# MD015A_MCU_F5529.net
KiCad netlist of a schematic drawn in Altium Designer
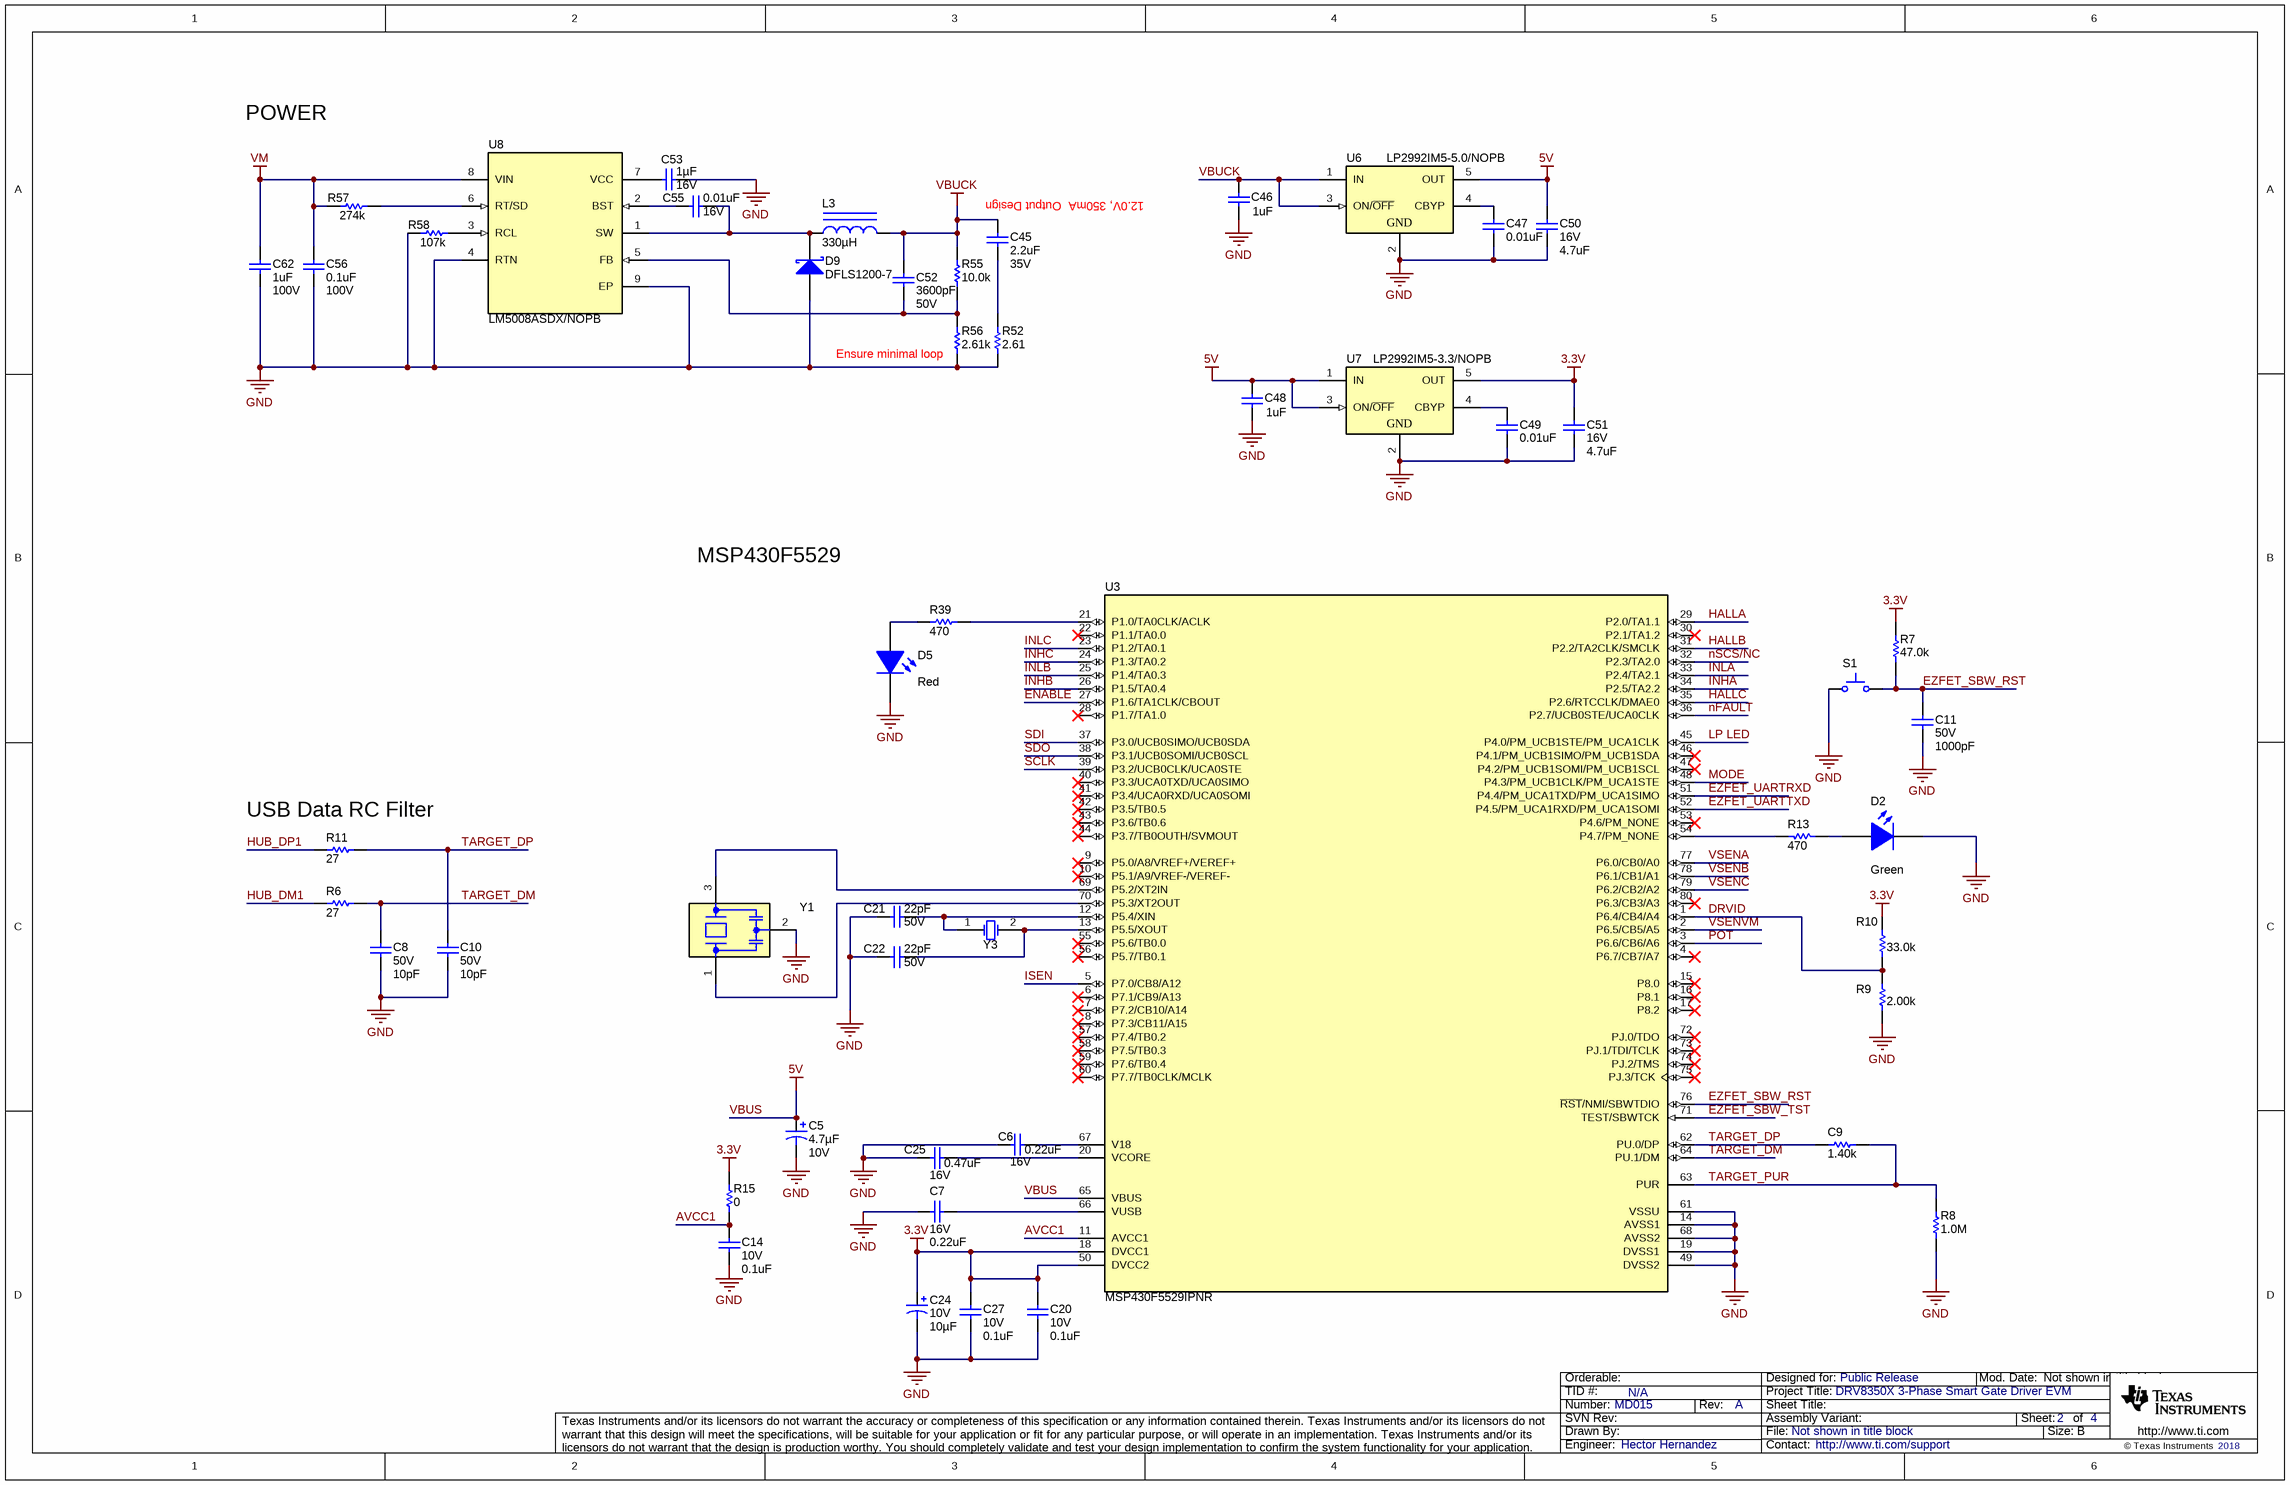
[diagram p0: MD015A_MCU_F5529.SchDoc]

(export (version "E")
  (design (tool "Eeschema 10.0.6"))
  (components
    (comp (ref "C5")
      (value "T55A475M010C0500")
      (footprint "3216-18")
      (description "CAP, Tantalum Polymer, 4.7 µF, 10 V,+/- 20%, 0.5 ohm, 3216-18 SMD")
      (fields
        (field (name "VALUEDISPLAYED") "4.7µF")
        (field (name "VDC_V") "10V")
        (field (name "MANUFACTURER") "Vishay-Sprague")
      )
      (libsource (lib "Altium Vault - TI") (part "Cap_Polarized"))
    )
    (comp (ref "C6")
      (value "C1005X5R1C224K050BB")
      (footprint "0402L")
      (description "CAP, CERM, 0.22 uF, 16 V, +/- 10%, X5R, 0402")
      (fields
        (field (name "MANUFACTURER") "TDK")
        (field (name "VDC_V") "16V")
        (field (name "VALUEDISPLAYED") "0.22uF")
        (field (name "PUBLISHER") "Texas Instruments")
      )
      (libsource (lib "Altium Vault - TI") (part "Capacitor"))
    )
    (comp (ref "C7")
      (value "C1005X5R1C224K050BB")
      (footprint "0402L")
      (description "CAP, CERM, 0.22 uF, 16 V, +/- 10%, X5R, 0402")
      (fields
        (field (name "MANUFACTURER") "TDK")
        (field (name "VDC_V") "16V")
        (field (name "VALUEDISPLAYED") "0.22uF")
        (field (name "PUBLISHER") "Texas Instruments")
      )
      (libsource (lib "Altium Vault - TI") (part "Capacitor"))
    )
    (comp (ref "C8")
      (value "500R07S100JV4T")
      (footprint "0402L")
      (description "CAP, CERM, 10 pF, 50 V, +/- 5%, C0G/NP0, 0402")
      (fields
        (field (name "MANUFACTURER") "Johanson Technology")
        (field (name "VDC_V") "50V")
        (field (name "VALUEDISPLAYED") "10pF")
        (field (name "PUBLISHER") "Texas Instruments")
      )
      (libsource (lib "Altium Vault - TI") (part "Capacitor"))
    )
    (comp (ref "C9")
      (value "ERJ-2RKF1401X")
      (footprint "0402L")
      (description "RES, 1.40 k, 1%, 0.1 W, 0402")
      (fields
        (field (name "MANUFACTURER") "Panasonic")
        (field (name "VALUEDISPLAYED") "1.40k")
        (field (name "PUBLISHER") "Texas Instruments")
      )
      (libsource (lib "Altium Vault - TI") (part "Resistor"))
    )
    (comp (ref "C10")
      (value "500R07S100JV4T")
      (footprint "0402L")
      (description "CAP, CERM, 10 pF, 50 V, +/- 5%, C0G/NP0, 0402")
      (fields
        (field (name "MANUFACTURER") "Johanson Technology")
        (field (name "VDC_V") "50V")
        (field (name "VALUEDISPLAYED") "10pF")
        (field (name "PUBLISHER") "Texas Instruments")
      )
      (libsource (lib "Altium Vault - TI") (part "Capacitor"))
    )
    (comp (ref "C11")
      (value "885012205061")
      (footprint "0402L")
      (description "CAP, CERM, 1000 pF, 50 V, +/- 10%, X7R, 0402")
      (fields
        (field (name "MANUFACTURER") "Wurth Elektronik")
        (field (name "VDC_V") "50V")
        (field (name "VALUEDISPLAYED") "1000pF")
        (field (name "PUBLISHER") "Texas Instruments")
      )
      (libsource (lib "Altium Vault - TI") (part "Capacitor"))
    )
    (comp (ref "C14")
      (value "885012105010")
      (footprint "0402L")
      (description "CAP, CERM, 0.1 uF, 10 V, +/- 20%, X5R, 0402")
      (fields
        (field (name "MANUFACTURER") "Wurth Elektronik")
        (field (name "VDC_V") "10V")
        (field (name "VALUEDISPLAYED") "0.1uF")
        (field (name "PUBLISHER") "Texas Instruments")
      )
      (libsource (lib "Altium Vault - TI") (part "Capacitor"))
    )
    (comp (ref "C20")
      (value "885012105010")
      (footprint "0402L")
      (description "CAP, CERM, 0.1 uF, 10 V, +/- 20%, X5R, 0402")
      (fields
        (field (name "MANUFACTURER") "Wurth Elektronik")
        (field (name "VDC_V") "10V")
        (field (name "VALUEDISPLAYED") "0.1uF")
        (field (name "PUBLISHER") "Texas Instruments")
      )
      (libsource (lib "Altium Vault - TI") (part "Capacitor"))
    )
    (comp (ref "C21")
      (value "C1005C0G1H220J050BA")
      (footprint "0402L")
      (description "CAP, CERM, 22 pF, 50 V, +/- 5%, C0G/NP0, 0402")
      (fields
        (field (name "MANUFACTURER") "TDK")
        (field (name "VDC_V") "50V")
        (field (name "VALUEDISPLAYED") "22pF")
        (field (name "PUBLISHER") "Texas Instruments")
      )
      (libsource (lib "Altium Vault - TI") (part "Capacitor"))
    )
    (comp (ref "C22")
      (value "C1005C0G1H220J050BA")
      (footprint "0402L")
      (description "CAP, CERM, 22 pF, 50 V, +/- 5%, C0G/NP0, 0402")
      (fields
        (field (name "MANUFACTURER") "TDK")
        (field (name "VDC_V") "50V")
        (field (name "VALUEDISPLAYED") "22pF")
        (field (name "PUBLISHER") "Texas Instruments")
      )
      (libsource (lib "Altium Vault - TI") (part "Capacitor"))
    )
    (comp (ref "C24")
      (value "T520A106M010ATE080")
      (footprint "3216-18")
      (description "CAP, Tantalum Polymer, 10 µF, 10 V,+/- 20%, 0.08 ohm, 3216-18 SMD")
      (fields
        (field (name "VDC_V") "10V")
        (field (name "MANUFACTURER") "Kemet")
        (field (name "VALUEDISPLAYED") "10µF")
      )
      (libsource (lib "Altium Vault - TI") (part "Cap_Polarized"))
    )
    (comp (ref "C25")
      (value "GCM188R71C474KA55D")
      (footprint "0603L")
      (description "CAP, CERM, 0.47 uF, 16 V, +/- 10%, X7R, AEC-Q200 Grade 1, 0603")
      (fields
        (field (name "MANUFACTURER") "MuRata")
        (field (name "VDC_V") "16V")
        (field (name "VALUEDISPLAYED") "0.47uF")
        (field (name "PUBLISHER") "Texas Instruments")
      )
      (libsource (lib "Altium Vault - TI") (part "Capacitor"))
    )
    (comp (ref "C27")
      (value "885012105010")
      (footprint "0402L")
      (description "CAP, CERM, 0.1 uF, 10 V, +/- 20%, X5R, 0402")
      (fields
        (field (name "MANUFACTURER") "Wurth Elektronik")
        (field (name "VDC_V") "10V")
        (field (name "VALUEDISPLAYED") "0.1uF")
        (field (name "PUBLISHER") "Texas Instruments")
      )
      (libsource (lib "Altium Vault - TI") (part "Capacitor"))
    )
    (comp (ref "C45")
      (value "C2012X7R1V225K085AC")
      (footprint "0805L")
      (description "CAP, CERM, 2.2 uF, 35 V, +/- 10%, X7R, 0805")
      (fields
        (field (name "MANUFACTURER") "TDK")
        (field (name "VALUEDISPLAYED") "2.2uF")
        (field (name "VDC_V") "35V")
        (field (name "PUBLISHER") "Texas Instruments")
      )
      (libsource (lib "Altium Vault - TI") (part "Capacitor"))
    )
    (comp (ref "C46")
      (value "CL21B105KBFNNNE")
      (footprint "0805L")
      (description "CAP, CERM, 1 uF, 50 V, +/- 10%, X7R, 0805")
      (fields
        (field (name "MANUFACTURER") "Samsung Electro-Mechanics")
        (field (name "VALUEDISPLAYED") "1uF")
        (field (name "PUBLISHER") "Texas Instruments")
      )
      (libsource (lib "Altium Vault - TI") (part "CMP-0007994-2"))
    )
    (comp (ref "C47")
      (value "C0603C103K4RACTU")
      (footprint "0603L")
      (description "CAP, CERM, 0.01 uF, 16 V, +/- 10%, X7R, 0603")
      (fields
        (field (name "VALUEDISPLAYED") "0.01uF")
        (field (name "MANUFACTURER") "Kemet")
        (field (name "PUBLISHER") "Texas Instruments")
      )
      (libsource (lib "Altium Vault - TI") (part "Capacitor"))
    )
    (comp (ref "C48")
      (value "CL21B105KBFNNNE")
      (footprint "0805L")
      (description "CAP, CERM, 1 uF, 50 V, +/- 10%, X7R, 0805")
      (fields
        (field (name "MANUFACTURER") "Samsung Electro-Mechanics")
        (field (name "VALUEDISPLAYED") "1uF")
        (field (name "PUBLISHER") "Texas Instruments")
      )
      (libsource (lib "Altium Vault - TI") (part "CMP-0007994-2"))
    )
    (comp (ref "C49")
      (value "C0603C103K4RACTU")
      (footprint "0603L")
      (description "CAP, CERM, 0.01 uF, 16 V, +/- 10%, X7R, 0603")
      (fields
        (field (name "VALUEDISPLAYED") "0.01uF")
        (field (name "MANUFACTURER") "Kemet")
        (field (name "PUBLISHER") "Texas Instruments")
      )
      (libsource (lib "Altium Vault - TI") (part "Capacitor"))
    )
    (comp (ref "C50")
      (value "GRM21BR71C475KA73L")
      (footprint "0805L")
      (description "CAP, CERM, 4.7 uF, 16 V, +/- 10%, X7R, 0805")
      (fields
        (field (name "MANUFACTURER") "MuRata")
        (field (name "VDC_V") "16V")
        (field (name "VALUEDISPLAYED") "4.7uF")
        (field (name "PUBLISHER") "Texas Instruments")
      )
      (libsource (lib "Altium Vault - TI") (part "Capacitor"))
    )
    (comp (ref "C51")
      (value "GRM21BR71C475KA73L")
      (footprint "0805L")
      (description "CAP, CERM, 4.7 uF, 16 V, +/- 10%, X7R, 0805")
      (fields
        (field (name "MANUFACTURER") "MuRata")
        (field (name "VDC_V") "16V")
        (field (name "VALUEDISPLAYED") "4.7uF")
        (field (name "PUBLISHER") "Texas Instruments")
      )
      (libsource (lib "Altium Vault - TI") (part "Capacitor"))
    )
    (comp (ref "C52")
      (value "GRM1885C1H362JA01D")
      (footprint "0603L")
      (description "CAP, CERM, 3600 pF, 50 V, +/- 5%, C0G/NP0, 0603")
      (fields
        (field (name "MANUFACTURER") "MuRata")
        (field (name "VALUEDISPLAYED") "3600pF")
        (field (name "VDC_V") "50V")
        (field (name "PUBLISHER") "Texas Instruments")
      )
      (libsource (lib "Altium Vault - TI") (part "Capacitor"))
    )
    (comp (ref "C53")
      (value "CL10B105KO8VPNC")
      (footprint "0603")
      (description "CAP, CERM, 1 µF, 16 V,+/- 10%, X7R, AEC-Q200 Grade 1, 0603")
      (fields
        (field (name "VDC_V") "16V")
        (field (name "MANUFACTURER") "Samsung Electro-Mechanics")
        (field (name "VALUEDISPLAYED") "1µF")
      )
      (libsource (lib "Altium Vault - TI") (part "Capacitor"))
    )
    (comp (ref "C55")
      (value "C0603C103K4RACTU")
      (footprint "0603L")
      (description "CAP, CERM, 0.01 uF, 16 V, +/- 10%, X7R, 0603")
      (fields
        (field (name "MANUFACTURER") "Kemet")
        (field (name "VALUEDISPLAYED") "0.01uF")
        (field (name "VDC_V") "16V")
        (field (name "PUBLISHER") "Texas Instruments")
      )
      (libsource (lib "Altium Vault - TI") (part "Capacitor"))
    )
    (comp (ref "C56")
      (value "C2012X7R2A104K125AA")
      (footprint "0805_HV")
      (description "CAP, CERM, 0.1 uF, 100 V, +/- 10%, X7R, 0805")
      (fields
        (field (name "MANUFACTURER") "TDK")
        (field (name "VALUEDISPLAYED") "0.1uF")
        (field (name "VDC_V") "100V")
        (field (name "PUBLISHER") "Texas Instruments")
      )
      (libsource (lib "Altium Vault - TI") (part "Capacitor"))
    )
    (comp (ref "C62")
      (value "CL31B105KCHNNNE")
      (footprint "1206_180")
      (description "CAP, CERM, 1 uF, 100 V, +/- 10%, X7R, 1206")
      (fields
        (field (name "MANUFACTURER") "Samsung")
        (field (name "VALUEDISPLAYED") "1uF")
        (field (name "VDC_V") "100V")
        (field (name "PUBLISHER") "Texas Instruments")
      )
      (libsource (lib "Altium Vault - TI") (part "Capacitor"))
    )
    (comp (ref "D2")
      (value "Green")
      (footprint "LED_LTST-C190")
      (description "LED, Green, SMD")
      (fields (field (name "MANUFACTURER") "Lite-On") (field (name "PARTNUMBER") "LTST-C190GKT"))
      (libsource (lib "Altium Vault - TI") (part "LED"))
    )
    (comp (ref "D5")
      (value "Red")
      (footprint "LED_LTST-C190_Red")
      (description "LED, Red, SMD")
      (fields (field (name "MANUFACTURER") "Lite-On") (field (name "PARTNUMBER") "LTST-C190CKT"))
      (libsource (lib "Altium Vault - TI") (part "LED"))
    )
    (comp (ref "D9")
      (value "DFLS1200-7")
      (footprint "PowerDI123")
      (description "Diode, Schottky, 200 V, 1 A, PowerDI123")
      (fields (field (name "MANUFACTURER") "Diodes Inc."))
      (libsource (lib "Altium Vault - TI") (part "DIODE_SCHOTTKY"))
    )
    (comp (ref "L3")
      (value "74404084331")
      (footprint "WE-LQS_8040")
      (description "Inductor, Shielded, 330 µH, 0.66 A, 1.1245 ohm, SMD")
      (fields (field (name "MANUFACTURER") "Wurth Elektronik") (field (name "VALUEDISPLAYED") "330µH"))
      (libsource (lib "Altium Vault - TI") (part "Inductor_Iron"))
    )
    (comp (ref "R6")
      (value "CRCW040227R0JNED")
      (footprint "0402L")
      (description "RES, 27, 5%, 0.063 W, AEC-Q200 Grade 0, 0402")
      (fields (field (name "MANUFACTURER") "Vishay-Dale") (field (name "VALUEDISPLAYED") "27"))
      (libsource (lib "Altium Vault - TI") (part "Resistor"))
    )
    (comp (ref "R7")
      (value "RC0402FR-0747KL")
      (footprint "0402L")
      (description "RES, 47.0 k, 1%, 0.0625 W, 0402")
      (fields
        (field (name "MANUFACTURER") "Yageo America")
        (field (name "VALUEDISPLAYED") "47.0k")
        (field (name "PUBLISHER") "Texas Instruments")
      )
      (libsource (lib "Altium Vault - TI") (part "Resistor"))
    )
    (comp (ref "R8")
      (value "CRCW04021M00JNED")
      (footprint "0402L")
      (description "RES, 1.0 M, 5%, 0.063 W, AEC-Q200 Grade 0, 0402")
      (fields (field (name "MANUFACTURER") "Vishay-Dale") (field (name "VALUEDISPLAYED") "1.0M"))
      (libsource (lib "Altium Vault - TI") (part "Resistor"))
    )
    (comp (ref "R9")
      (value "RC0603FR-072KL")
      (footprint "0603L")
      (description "RES, 2.00 k, 1%, 0.1 W, 0603")
      (fields (field (name "MANUFACTURER") "Yageo") (field (name "VALUEDISPLAYED") "2.00k"))
      (libsource (lib "Altium Vault - TI") (part "Resistor"))
    )
    (comp (ref "R10")
      (value "MCT06030C3302FP500")
      (footprint "0603L")
      (description "RES, 33.0 k, 1%, 0.125 W, 0603")
      (fields
        (field (name "MANUFACTURER") "Vishay/Beyschlag")
        (field (name "VALUEDISPLAYED") "33.0k")
        (field (name "PUBLISHER") "Texas Instruments")
      )
      (libsource (lib "Altium Vault - TI") (part "Resistor"))
    )
    (comp (ref "R11")
      (value "CRCW040227R0JNED")
      (footprint "0402L")
      (description "RES, 27, 5%, 0.063 W, AEC-Q200 Grade 0, 0402")
      (fields (field (name "MANUFACTURER") "Vishay-Dale") (field (name "VALUEDISPLAYED") "27"))
      (libsource (lib "Altium Vault - TI") (part "Resistor"))
    )
    (comp (ref "R13")
      (value "ERJ-2RKF4700X")
      (footprint "0402L")
      (description "RES, 470, 1%, 0.1 W, AEC-Q200 Grade 0, 0402")
      (fields
        (field (name "MANUFACTURER") "Panasonic")
        (field (name "VALUEDISPLAYED") "470")
        (field (name "PUBLISHER") "Texas Instruments")
      )
      (libsource (lib "Altium Vault - TI") (part "Resistor"))
    )
    (comp (ref "R15")
      (value "MCR01MZPJ000")
      (footprint "0402L")
      (description "RES, 0, 5%, 0.063 W, 0402")
      (fields
        (field (name "MANUFACTURER") "Rohm")
        (field (name "VALUEDISPLAYED") "0")
        (field (name "PUBLISHER") "Texas Instruments")
      )
      (libsource (lib "Altium Vault - TI") (part "Resistor"))
    )
    (comp (ref "R39")
      (value "ERJ-2RKF4700X")
      (footprint "0402L")
      (description "RES, 470, 1%, 0.1 W, AEC-Q200 Grade 0, 0402")
      (fields
        (field (name "MANUFACTURER") "Panasonic")
        (field (name "VALUEDISPLAYED") "470")
        (field (name "PUBLISHER") "Texas Instruments")
      )
      (libsource (lib "Altium Vault - TI") (part "Resistor"))
    )
    (comp (ref "R52")
      (value "CRCW06032R61FKEA")
      (footprint "0603L")
      (description "RES, 2.61, 1%, 0.1 W, AEC-Q200 Grade 0, 0603")
      (fields (field (name "MANUFACTURER") "Vishay-Dale") (field (name "VALUEDISPLAYED") "2.61"))
      (libsource (lib "Altium Vault - TI") (part "Resistor"))
    )
    (comp (ref "R55")
      (value "RG1608P-103-B-T5")
      (footprint "0603L")
      (description "RES, 10.0 k, 0.1%, 0.1 W, 0603")
      (fields
        (field (name "MANUFACTURER") "Susumu Co Ltd")
        (field (name "VALUEDISPLAYED") "10.0k")
        (field (name "PUBLISHER") "Texas Instruments")
      )
      (libsource (lib "Altium Vault - TI") (part "Resistor"))
    )
    (comp (ref "R56")
      (value "RG1608P-2611-B-T5")
      (footprint "0603L")
      (description "RES, 2.61 k, 0.1%, 0.1 W, 0603")
      (fields
        (field (name "MANUFACTURER") "Susumu Co Ltd")
        (field (name "VALUEDISPLAYED") "2.61k")
        (field (name "PUBLISHER") "Texas Instruments")
      )
      (libsource (lib "Altium Vault - TI") (part "Resistor"))
    )
    (comp (ref "R57")
      (value "RC0603FR-07274KL")
      (footprint "0603_HV")
      (description "RES, 274 k, 1%, 0.1 W, 0603")
      (fields (field (name "MANUFACTURER") "Yageo") (field (name "VALUEDISPLAYED") "274k"))
      (libsource (lib "Altium Vault - TI") (part "Resistor"))
    )
    (comp (ref "R58")
      (value "RC0603FR-07107KL")
      (footprint "0603_HV")
      (description "RES, 107 k, 1%, 0.1 W, 0603")
      (fields (field (name "MANUFACTURER") "Yageo") (field (name "VALUEDISPLAYED") "107k"))
      (libsource (lib "Altium Vault - TI") (part "Resistor"))
    )
    (comp (ref "S1")
      (value "EVQ-21505R")
      (footprint "SW_EVQ-21x05")
      (description "Switch, Tactile, SPST-NO, 0.02A, 15V, TH")
      (fields (field (name "MANUFACTURER") "Panasonic") (field (name "PUBLISHER") "Texas Instruments"))
      (libsource (lib "Altium Vault - TI") (part "KSR221GLFS"))
    )
    (comp (ref "U3")
      (value "MSP430F5529IPNR")
      (footprint "PN0080A_L")
      (fields (field (name "MANUFACTURER") "Texas Instruments") (field (name "PARTNUMBER") "MSP430F5529IPNR"))
      (libsource (lib "Altium Vault - TI") (part "TI-MSP430F552X_A-PN80"))
    )
    (comp (ref "U6")
      (value "LP2992IM5-5.0/NOPB")
      (footprint "DBV0005A_L")
      (description "Micropower 250 mA Low-Noise Ultra Low-Dropout Regulator, DBV0005A (SOT-23-5)")
      (fields
        (field (name "MANUFACTURER") "Texas Instruments")
        (field (name "PARTNUMBER") "LP2992IM5-5.0/NOPB")
      )
      (libsource (lib "Altium Vault - TI") (part "PM-REG-LP2985-SOT5"))
    )
    (comp (ref "U7")
      (value "LP2992IM5-3.3/NOPB")
      (footprint "DBV0005A_L")
      (description "Micropower 250 mA Low-Noise Ultra Low-Dropout Regulator, DBV0005A (SOT-23-5)")
      (fields
        (field (name "MANUFACTURER") "Texas Instruments")
        (field (name "PARTNUMBER") "LP2992IM5-3.3/NOPB")
      )
      (libsource (lib "Altium Vault - TI") (part "PM-REG-LP2985-SOT5"))
    )
    (comp (ref "U8")
      (value "LM5008ASDX/NOPB")
      (footprint "NGU0008B")
      (description "100V, 350 mA Constant On-Time Buck Switching Regulator, 8-pin LLP, Pb-Free")
      (fields (field (name "MANUFACTURER") "Texas Instruments") (field (name "PARTNUMBER") "LM5008ASDX/NOPB"))
      (libsource (lib "Altium Vault - TI") (part "PM-SWREG-LM5008A-9"))
    )
    (comp (ref "Y1")
      (value "CSTNR4M00GH5L000R0")
      (footprint "MuRata_CSTNR")
      (description "Oscillator, 4 MHz, 700 ppm, 39 pF, SMD")
      (fields (field (name "MANUFACTURER") "MuRata"))
      (libsource (lib "Altium Vault - TI") (part "OSC_CSTCE"))
    )
    (comp (ref "Y3")
      (value "FC-135R 32.7680KA-A3")
      (footprint "Epson_FC-135")
      (description "Crystal, 32.768 KHz, 20 ppm, 12.5 pF, AEC-Q200 Grade 3, SMD")
      (fields (field (name "MANUFACTURER") "Epson"))
      (libsource (lib "Altium Vault - TI") (part "Xtal"))
    )
  )
  (nets
    (net (code "1") (name "/AVCC1") (class "Default")
      (node (ref "C14") (pin "1") (pinfunction "1_1") (pintype "passive"))
      (node (ref "R15") (pin "1") (pinfunction "1_1") (pintype "passive"))
      (node (ref "U3") (pin "11") (pinfunction "AVCC1_11") (pintype "power_in"))
    )
    (net (code "2") (name "/DRVID") (class "Default")
      (node (ref "R10") (pin "1") (pinfunction "1_1") (pintype "passive"))
      (node (ref "R9") (pin "2") (pinfunction "2_2") (pintype "passive"))
      (node (ref "U3") (pin "1") (pinfunction "P6.4/CB4/A4_1") (pintype "bidirectional"))
    )
    (net (code "3") (name "/ENABLE") (class "Default")
      (node (ref "U3") (pin "27") (pinfunction "P1.6/TA1CLK/CBOUT_27") (pintype "bidirectional"))
    )
    (net (code "4") (name "/EZFET_SBW_RST") (class "Default")
      (node (ref "C11") (pin "1") (pinfunction "1_1") (pintype "passive"))
      (node (ref "R7") (pin "1") (pinfunction "1_1") (pintype "passive"))
      (node (ref "S1") (pin "2") (pinfunction "2_2") (pintype "passive"))
      (node (ref "U3") (pin "76") (pinfunction "~{RST}/NMI/SBWTDIO_76") (pintype "bidirectional"))
    )
    (net (code "5") (name "/EZFET_SBW_TST") (class "Default")
      (node (ref "U3") (pin "71") (pinfunction "TEST/SBWTCK_71") (pintype "input"))
    )
    (net (code "6") (name "/EZFET_UARTRXD") (class "Default")
      (node (ref "U3") (pin "51") (pinfunction "P4.4/PM_UCA1TXD/PM_UCA1SIMO_51") (pintype "bidirectional"))
    )
    (net (code "7") (name "/EZFET_UARTTXD") (class "Default")
      (node (ref "U3") (pin "52") (pinfunction "P4.5/PM_UCA1RXD/PM_UCA1SOMI_52") (pintype "bidirectional"))
    )
    (net (code "8") (name "/HALLA") (class "Default")
      (node (ref "U3") (pin "29") (pinfunction "P2.0/TA1.1_29") (pintype "bidirectional"))
    )
    (net (code "9") (name "/HALLB") (class "Default")
      (node (ref "U3") (pin "31") (pinfunction "P2.2/TA2CLK/SMCLK_31") (pintype "bidirectional"))
    )
    (net (code "10") (name "/HALLC") (class "Default")
      (node (ref "U3") (pin "35") (pinfunction "P2.6/RTCCLK/DMAE0_35") (pintype "bidirectional"))
    )
    (net (code "11") (name "/HUB_DM1") (class "Default")
      (node (ref "R6") (pin "2") (pinfunction "2_2") (pintype "passive"))
    )
    (net (code "12") (name "/HUB_DP1") (class "Default")
      (node (ref "R11") (pin "2") (pinfunction "2_2") (pintype "passive"))
    )
    (net (code "13") (name "/INHA") (class "Default")
      (node (ref "U3") (pin "34") (pinfunction "P2.5/TA2.2_34") (pintype "bidirectional"))
    )
    (net (code "14") (name "/INHB") (class "Default")
      (node (ref "U3") (pin "26") (pinfunction "P1.5/TA0.4_26") (pintype "bidirectional"))
    )
    (net (code "15") (name "/INHC") (class "Default")
      (node (ref "U3") (pin "24") (pinfunction "P1.3/TA0.2_24") (pintype "bidirectional"))
    )
    (net (code "16") (name "/INLA") (class "Default")
      (node (ref "U3") (pin "33") (pinfunction "P2.4/TA2.1_33") (pintype "bidirectional"))
    )
    (net (code "17") (name "/INLB") (class "Default")
      (node (ref "U3") (pin "25") (pinfunction "P1.4/TA0.3_25") (pintype "bidirectional"))
    )
    (net (code "18") (name "/INLC") (class "Default")
      (node (ref "U3") (pin "23") (pinfunction "P1.2/TA0.1_23") (pintype "bidirectional"))
    )
    (net (code "19") (name "/ISEN") (class "Default")
      (node (ref "U3") (pin "5") (pinfunction "P7.0/CB8/A12_5") (pintype "bidirectional"))
    )
    (net (code "20") (name "/LP LED") (class "Default")
      (node (ref "U3") (pin "45") (pinfunction "P4.0/PM_UCB1STE/PM_UCA1CLK_45") (pintype "bidirectional"))
    )
    (net (code "21") (name "/MODE") (class "Default")
      (node (ref "U3") (pin "48") (pinfunction "P4.3/PM_UCB1CLK/PM_UCA1STE_48") (pintype "bidirectional"))
    )
    (net (code "22") (name "/POT") (class "Default")
      (node (ref "U3") (pin "3") (pinfunction "P6.6/CB6/A6_3") (pintype "bidirectional"))
    )
    (net (code "23") (name "/SCLK") (class "Default")
      (node (ref "U3") (pin "39") (pinfunction "P3.2/UCB0CLK/UCA0STE_39") (pintype "bidirectional"))
    )
    (net (code "24") (name "/SDI") (class "Default")
      (node (ref "U3") (pin "37") (pinfunction "P3.0/UCB0SIMO/UCB0SDA_37") (pintype "bidirectional"))
    )
    (net (code "25") (name "/SDO") (class "Default")
      (node (ref "U3") (pin "38") (pinfunction "P3.1/UCB0SOMI/UCB0SCL_38") (pintype "bidirectional"))
    )
    (net (code "26") (name "/TARGET_DM") (class "Default")
      (node (ref "C8") (pin "2") (pinfunction "2_2") (pintype "passive"))
      (node (ref "R6") (pin "1") (pinfunction "1_1") (pintype "passive"))
      (node (ref "U3") (pin "64") (pinfunction "PU.1/DM_64") (pintype "bidirectional"))
    )
    (net (code "27") (name "/TARGET_DP") (class "Default")
      (node (ref "C10") (pin "2") (pinfunction "2_2") (pintype "passive"))
      (node (ref "C9") (pin "1") (pinfunction "1_1") (pintype "passive"))
      (node (ref "R11") (pin "1") (pinfunction "1_1") (pintype "passive"))
      (node (ref "U3") (pin "62") (pinfunction "PU.0/DP_62") (pintype "bidirectional"))
    )
    (net (code "28") (name "/TARGET_PUR") (class "Default")
      (node (ref "C9") (pin "2") (pinfunction "2_2") (pintype "passive"))
      (node (ref "R8") (pin "2") (pinfunction "2_2") (pintype "passive"))
      (node (ref "U3") (pin "63") (pinfunction "PUR_63") (pintype "passive"))
    )
    (net (code "29") (name "/VSENA") (class "Default")
      (node (ref "U3") (pin "77") (pinfunction "P6.0/CB0/A0_77") (pintype "bidirectional"))
    )
    (net (code "30") (name "/VSENB") (class "Default")
      (node (ref "U3") (pin "78") (pinfunction "P6.1/CB1/A1_78") (pintype "bidirectional"))
    )
    (net (code "31") (name "/VSENC") (class "Default")
      (node (ref "U3") (pin "79") (pinfunction "P6.2/CB2/A2_79") (pintype "bidirectional"))
    )
    (net (code "32") (name "/VSENVM") (class "Default")
      (node (ref "U3") (pin "2") (pinfunction "P6.5/CB5/A5_2") (pintype "bidirectional"))
    )
    (net (code "33") (name "/nFAULT") (class "Default")
      (node (ref "U3") (pin "36") (pinfunction "P2.7/UCB0STE/UCA0CLK_36") (pintype "bidirectional"))
    )
    (net (code "34") (name "/nSCS{slash}NC") (class "Default")
      (node (ref "U3") (pin "32") (pinfunction "P2.3/TA2.0_32") (pintype "bidirectional"))
    )
    (net (code "35") (name "3.3V") (class "Default")
      (node (ref "C20") (pin "2") (pinfunction "2_2") (pintype "passive"))
      (node (ref "C24") (pin "1") (pinfunction "+_1") (pintype "passive"))
      (node (ref "C27") (pin "2") (pinfunction "2_2") (pintype "passive"))
      (node (ref "C51") (pin "1") (pinfunction "1_1") (pintype "passive"))
      (node (ref "R10") (pin "2") (pinfunction "2_2") (pintype "passive"))
      (node (ref "R15") (pin "2") (pinfunction "2_2") (pintype "passive"))
      (node (ref "R7") (pin "2") (pinfunction "2_2") (pintype "passive"))
      (node (ref "U3") (pin "18") (pinfunction "DVCC1_18") (pintype "power_in"))
      (node (ref "U3") (pin "50") (pinfunction "DVCC2_50") (pintype "power_in"))
      (node (ref "U7") (pin "5") (pinfunction "OUT_5") (pintype "power_in"))
    )
    (net (code "36") (name "5V") (class "Default")
      (node (ref "C48") (pin "1") (pinfunction "1_1") (pintype "passive"))
      (node (ref "C5") (pin "1") (pinfunction "+_1") (pintype "passive"))
      (node (ref "C50") (pin "1") (pinfunction "1_1") (pintype "passive"))
      (node (ref "U3") (pin "65") (pinfunction "VBUS_65") (pintype "power_in"))
      (node (ref "U6") (pin "5") (pinfunction "OUT_5") (pintype "power_in"))
      (node (ref "U7") (pin "1") (pinfunction "IN_1") (pintype "power_in"))
      (node (ref "U7") (pin "3") (pinfunction "ON/~{OFF}_3") (pintype "input"))
    )
    (net (code "37") (name "GND") (class "Default")
      (node (ref "C10") (pin "1") (pinfunction "1_1") (pintype "passive"))
      (node (ref "C11") (pin "2") (pinfunction "2_2") (pintype "passive"))
      (node (ref "C14") (pin "2") (pinfunction "2_2") (pintype "passive"))
      (node (ref "C20") (pin "1") (pinfunction "1_1") (pintype "passive"))
      (node (ref "C21") (pin "1") (pinfunction "1_1") (pintype "passive"))
      (node (ref "C22") (pin "1") (pinfunction "1_1") (pintype "passive"))
      (node (ref "C24") (pin "2") (pinfunction "-_2") (pintype "passive"))
      (node (ref "C25") (pin "1") (pinfunction "1_1") (pintype "passive"))
      (node (ref "C27") (pin "1") (pinfunction "1_1") (pintype "passive"))
      (node (ref "C46") (pin "2") (pinfunction "2_2") (pintype "passive"))
      (node (ref "C47") (pin "2") (pinfunction "2_2") (pintype "passive"))
      (node (ref "C48") (pin "2") (pinfunction "2_2") (pintype "passive"))
      (node (ref "C49") (pin "2") (pinfunction "2_2") (pintype "passive"))
      (node (ref "C5") (pin "2") (pinfunction "-_2") (pintype "passive"))
      (node (ref "C50") (pin "2") (pinfunction "2_2") (pintype "passive"))
      (node (ref "C51") (pin "2") (pinfunction "2_2") (pintype "passive"))
      (node (ref "C53") (pin "2") (pinfunction "2_2") (pintype "passive"))
      (node (ref "C56") (pin "2") (pinfunction "2_2") (pintype "passive"))
      (node (ref "C6") (pin "1") (pinfunction "1_1") (pintype "passive"))
      (node (ref "C62") (pin "2") (pinfunction "2_2") (pintype "passive"))
      (node (ref "C7") (pin "1") (pinfunction "1_1") (pintype "passive"))
      (node (ref "C8") (pin "1") (pinfunction "1_1") (pintype "passive"))
      (node (ref "D2") (pin "2") (pinfunction "K_2") (pintype "passive"))
      (node (ref "D5") (pin "2") (pinfunction "K_2") (pintype "passive"))
      (node (ref "D9") (pin "2") (pinfunction "A_2") (pintype "passive"))
      (node (ref "R52") (pin "1") (pinfunction "1_1") (pintype "passive"))
      (node (ref "R56") (pin "1") (pinfunction "1_1") (pintype "passive"))
      (node (ref "R58") (pin "1") (pinfunction "1_1") (pintype "passive"))
      (node (ref "R8") (pin "1") (pinfunction "1_1") (pintype "passive"))
      (node (ref "R9") (pin "1") (pinfunction "1_1") (pintype "passive"))
      (node (ref "S1") (pin "1") (pinfunction "1_1") (pintype "passive"))
      (node (ref "U3") (pin "14") (pinfunction "AVSS1_14") (pintype "power_in"))
      (node (ref "U3") (pin "19") (pinfunction "DVSS1_19") (pintype "power_in"))
      (node (ref "U3") (pin "49") (pinfunction "DVSS2_49") (pintype "power_in"))
      (node (ref "U3") (pin "61") (pinfunction "VSSU_61") (pintype "power_in"))
      (node (ref "U3") (pin "68") (pinfunction "AVSS2_68") (pintype "power_in"))
      (node (ref "U6") (pin "2") (pinfunction "GND_2") (pintype "power_in"))
      (node (ref "U7") (pin "2") (pinfunction "GND_2") (pintype "power_in"))
      (node (ref "U8") (pin "4") (pinfunction "RTN_4") (pintype "power_in"))
      (node (ref "U8") (pin "9") (pinfunction "EP_9") (pintype "power_in"))
      (node (ref "Y1") (pin "2") (pinfunction "GND_2") (pintype "passive"))
    )
    (net (code "38") (name "Net-(C45-Pad2)") (class "Default")
      (node (ref "C45") (pin "2") (pinfunction "2_2") (pintype "passive"))
      (node (ref "R52") (pin "2") (pinfunction "2_2") (pintype "passive"))
    )
    (net (code "39") (name "Net-(D2-A)") (class "Default")
      (node (ref "D2") (pin "1") (pinfunction "A_1") (pintype "passive"))
      (node (ref "R13") (pin "2") (pinfunction "2_2") (pintype "passive"))
    )
    (net (code "40") (name "Net-(D5-A)") (class "Default")
      (node (ref "D5") (pin "1") (pinfunction "A_1") (pintype "passive"))
      (node (ref "R39") (pin "2") (pinfunction "2_2") (pintype "passive"))
    )
    (net (code "41") (name "Net-(D9-K)") (class "Default")
      (node (ref "C55") (pin "1") (pinfunction "1_1") (pintype "passive"))
      (node (ref "D9") (pin "1") (pinfunction "K_1") (pintype "passive"))
      (node (ref "L3") (pin "1") (pinfunction "1_1") (pintype "passive"))
      (node (ref "U8") (pin "1") (pinfunction "SW_1") (pintype "power_in"))
    )
    (net (code "42") (name "Net-(U3-P1.0{slash}TA0CLK{slash}ACLK)") (class "Default")
      (node (ref "R39") (pin "1") (pinfunction "1_1") (pintype "passive"))
      (node (ref "U3") (pin "21") (pinfunction "P1.0/TA0CLK/ACLK_21") (pintype "bidirectional"))
    )
    (net (code "43") (name "Net-(U3-P4.7{slash}PM_NONE)") (class "Default")
      (node (ref "R13") (pin "1") (pinfunction "1_1") (pintype "passive"))
      (node (ref "U3") (pin "54") (pinfunction "P4.7/PM_NONE_54") (pintype "bidirectional"))
    )
    (net (code "44") (name "Net-(U3-P5.2{slash}XT2IN)") (class "Default")
      (node (ref "U3") (pin "69") (pinfunction "P5.2/XT2IN_69") (pintype "bidirectional"))
      (node (ref "Y1") (pin "3") (pinfunction "Out_3") (pintype "passive"))
    )
    (net (code "45") (name "Net-(U3-P5.3{slash}XT2OUT)") (class "Default")
      (node (ref "U3") (pin "70") (pinfunction "P5.3/XT2OUT_70") (pintype "bidirectional"))
      (node (ref "Y1") (pin "1") (pinfunction "In_1") (pintype "passive"))
    )
    (net (code "46") (name "Net-(U3-P5.4{slash}XIN)") (class "Default")
      (node (ref "C21") (pin "2") (pinfunction "2_2") (pintype "passive"))
      (node (ref "U3") (pin "12") (pinfunction "P5.4/XIN_12") (pintype "bidirectional"))
      (node (ref "Y3") (pin "1") (pinfunction "OSC1_1") (pintype "passive"))
    )
    (net (code "47") (name "Net-(U3-P5.5{slash}XOUT)") (class "Default")
      (node (ref "C22") (pin "2") (pinfunction "2_2") (pintype "passive"))
      (node (ref "U3") (pin "13") (pinfunction "P5.5/XOUT_13") (pintype "bidirectional"))
      (node (ref "Y3") (pin "2") (pinfunction "OSC2_2") (pintype "passive"))
    )
    (net (code "48") (name "Net-(U3-V18)") (class "Default")
      (node (ref "C6") (pin "2") (pinfunction "2_2") (pintype "passive"))
      (node (ref "U3") (pin "67") (pinfunction "V18_67") (pintype "passive"))
    )
    (net (code "49") (name "Net-(U3-VCORE)") (class "Default")
      (node (ref "C25") (pin "2") (pinfunction "2_2") (pintype "passive"))
      (node (ref "U3") (pin "20") (pinfunction "VCORE_20") (pintype "passive"))
    )
    (net (code "50") (name "Net-(U3-VUSB)") (class "Default")
      (node (ref "C7") (pin "2") (pinfunction "2_2") (pintype "passive"))
      (node (ref "U3") (pin "66") (pinfunction "VUSB_66") (pintype "power_in"))
    )
    (net (code "51") (name "Net-(U6-CBYP)") (class "Default")
      (node (ref "C47") (pin "1") (pinfunction "1_1") (pintype "passive"))
      (node (ref "U6") (pin "4") (pinfunction "CBYP_4") (pintype "passive"))
    )
    (net (code "52") (name "Net-(U7-CBYP)") (class "Default")
      (node (ref "C49") (pin "1") (pinfunction "1_1") (pintype "passive"))
      (node (ref "U7") (pin "4") (pinfunction "CBYP_4") (pintype "passive"))
    )
    (net (code "53") (name "Net-(U8-BST)") (class "Default")
      (node (ref "C55") (pin "2") (pinfunction "2_2") (pintype "passive"))
      (node (ref "U8") (pin "2") (pinfunction "BST_2") (pintype "input"))
    )
    (net (code "54") (name "Net-(U8-FB)") (class "Default")
      (node (ref "C52") (pin "2") (pinfunction "2_2") (pintype "passive"))
      (node (ref "R55") (pin "1") (pinfunction "1_1") (pintype "passive"))
      (node (ref "R56") (pin "2") (pinfunction "2_2") (pintype "passive"))
      (node (ref "U8") (pin "5") (pinfunction "FB_5") (pintype "input"))
    )
    (net (code "55") (name "Net-(U8-RCL)") (class "Default")
      (node (ref "R58") (pin "2") (pinfunction "2_2") (pintype "passive"))
      (node (ref "U8") (pin "3") (pinfunction "RCL_3") (pintype "input"))
    )
    (net (code "56") (name "Net-(U8-RT{slash}SD)") (class "Default")
      (node (ref "R57") (pin "2") (pinfunction "2_2") (pintype "passive"))
      (node (ref "U8") (pin "6") (pinfunction "RT/SD_6") (pintype "input"))
    )
    (net (code "57") (name "Net-(U8-VCC)") (class "Default")
      (node (ref "C53") (pin "1") (pinfunction "1_1") (pintype "passive"))
      (node (ref "U8") (pin "7") (pinfunction "VCC_7") (pintype "power_in"))
    )
    (net (code "58") (name "VBUCK") (class "Default")
      (node (ref "C45") (pin "1") (pinfunction "1_1") (pintype "passive"))
      (node (ref "C46") (pin "1") (pinfunction "1_1") (pintype "passive"))
      (node (ref "C52") (pin "1") (pinfunction "1_1") (pintype "passive"))
      (node (ref "L3") (pin "2") (pinfunction "2_2") (pintype "passive"))
      (node (ref "R55") (pin "2") (pinfunction "2_2") (pintype "passive"))
      (node (ref "U6") (pin "1") (pinfunction "IN_1") (pintype "power_in"))
      (node (ref "U6") (pin "3") (pinfunction "ON/~{OFF}_3") (pintype "input"))
    )
    (net (code "59") (name "VM") (class "Default")
      (node (ref "C56") (pin "1") (pinfunction "1_1") (pintype "passive"))
      (node (ref "C62") (pin "1") (pinfunction "1_1") (pintype "passive"))
      (node (ref "R57") (pin "1") (pinfunction "1_1") (pintype "passive"))
      (node (ref "U8") (pin "8") (pinfunction "VIN_8") (pintype "power_in"))
    )
    (net (code "60") (name "unconnected-(U3-P1.1{slash}TA0.0-Pad22)") (class "Default")
      (node (ref "U3") (pin "22") (pinfunction "P1.1/TA0.0_22") (pintype "bidirectional+no_connect"))
    )
    (net (code "61") (name "unconnected-(U3-P1.7{slash}TA1.0-Pad28)") (class "Default")
      (node (ref "U3") (pin "28") (pinfunction "P1.7/TA1.0_28") (pintype "bidirectional+no_connect"))
    )
    (net (code "62") (name "unconnected-(U3-P2.1{slash}TA1.2-Pad30)") (class "Default")
      (node (ref "U3") (pin "30") (pinfunction "P2.1/TA1.2_30") (pintype "bidirectional+no_connect"))
    )
    (net (code "63") (name "unconnected-(U3-P3.3{slash}UCA0TXD{slash}UCA0SIMO-Pad40)") (class "Default")
      (node (ref "U3") (pin "40") (pinfunction "P3.3/UCA0TXD/UCA0SIMO_40") (pintype "bidirectional+no_connect"))
    )
    (net (code "64") (name "unconnected-(U3-P3.4{slash}UCA0RXD{slash}UCA0SOMI-Pad41)") (class "Default")
      (node (ref "U3") (pin "41") (pinfunction "P3.4/UCA0RXD/UCA0SOMI_41") (pintype "bidirectional+no_connect"))
    )
    (net (code "65") (name "unconnected-(U3-P3.5{slash}TB0.5-Pad42)") (class "Default")
      (node (ref "U3") (pin "42") (pinfunction "P3.5/TB0.5_42") (pintype "bidirectional+no_connect"))
    )
    (net (code "66") (name "unconnected-(U3-P3.6{slash}TB0.6-Pad43)") (class "Default")
      (node (ref "U3") (pin "43") (pinfunction "P3.6/TB0.6_43") (pintype "bidirectional+no_connect"))
    )
    (net (code "67") (name "unconnected-(U3-P3.7{slash}TB0OUTH{slash}SVMOUT-Pad44)") (class "Default")
      (node (ref "U3") (pin "44") (pinfunction "P3.7/TB0OUTH/SVMOUT_44") (pintype "bidirectional+no_connect"))
    )
    (net (code "68") (name "unconnected-(U3-P4.1{slash}PM_UCB1SIMO{slash}PM_UCB1SDA-Pad46)") (class "Default")
      (node (ref "U3") (pin "46") (pinfunction "P4.1/PM_UCB1SIMO/PM_UCB1SDA_46") (pintype "bidirectional+no_connect"))
    )
    (net (code "69") (name "unconnected-(U3-P4.2{slash}PM_UCB1SOMI{slash}PM_UCB1SCL-Pad47)") (class "Default")
      (node (ref "U3") (pin "47") (pinfunction "P4.2/PM_UCB1SOMI/PM_UCB1SCL_47") (pintype "bidirectional+no_connect"))
    )
    (net (code "70") (name "unconnected-(U3-P4.6{slash}PM_NONE-Pad53)") (class "Default")
      (node (ref "U3") (pin "53") (pinfunction "P4.6/PM_NONE_53") (pintype "bidirectional+no_connect"))
    )
    (net (code "71") (name "unconnected-(U3-P5.0{slash}A8{slash}VREF+{slash}VEREF+-Pad9)") (class "Default")
      (node (ref "U3") (pin "9") (pinfunction "P5.0/A8/VREF+/VEREF+_9") (pintype "bidirectional+no_connect"))
    )
    (net (code "72") (name "unconnected-(U3-P5.1{slash}A9{slash}VREF-{slash}VEREF--Pad10)") (class "Default")
      (node (ref "U3") (pin "10") (pinfunction "P5.1/A9/VREF-/VEREF-_10") (pintype "bidirectional+no_connect"))
    )
    (net (code "73") (name "unconnected-(U3-P5.6{slash}TB0.0-Pad55)") (class "Default")
      (node (ref "U3") (pin "55") (pinfunction "P5.6/TB0.0_55") (pintype "bidirectional+no_connect"))
    )
    (net (code "74") (name "unconnected-(U3-P5.7{slash}TB0.1-Pad56)") (class "Default")
      (node (ref "U3") (pin "56") (pinfunction "P5.7/TB0.1_56") (pintype "bidirectional+no_connect"))
    )
    (net (code "75") (name "unconnected-(U3-P6.3{slash}CB3{slash}A3-Pad80)") (class "Default")
      (node (ref "U3") (pin "80") (pinfunction "P6.3/CB3/A3_80") (pintype "bidirectional+no_connect"))
    )
    (net (code "76") (name "unconnected-(U3-P6.7{slash}CB7{slash}A7-Pad4)") (class "Default")
      (node (ref "U3") (pin "4") (pinfunction "P6.7/CB7/A7_4") (pintype "bidirectional+no_connect"))
    )
    (net (code "77") (name "unconnected-(U3-P7.1{slash}CB9{slash}A13-Pad6)") (class "Default")
      (node (ref "U3") (pin "6") (pinfunction "P7.1/CB9/A13_6") (pintype "bidirectional+no_connect"))
    )
    (net (code "78") (name "unconnected-(U3-P7.2{slash}CB10{slash}A14-Pad7)") (class "Default")
      (node (ref "U3") (pin "7") (pinfunction "P7.2/CB10/A14_7") (pintype "bidirectional+no_connect"))
    )
    (net (code "79") (name "unconnected-(U3-P7.3{slash}CB11{slash}A15-Pad8)") (class "Default")
      (node (ref "U3") (pin "8") (pinfunction "P7.3/CB11/A15_8") (pintype "bidirectional+no_connect"))
    )
    (net (code "80") (name "unconnected-(U3-P7.4{slash}TB0.2-Pad57)") (class "Default")
      (node (ref "U3") (pin "57") (pinfunction "P7.4/TB0.2_57") (pintype "bidirectional+no_connect"))
    )
    (net (code "81") (name "unconnected-(U3-P7.5{slash}TB0.3-Pad58)") (class "Default")
      (node (ref "U3") (pin "58") (pinfunction "P7.5/TB0.3_58") (pintype "bidirectional+no_connect"))
    )
    (net (code "82") (name "unconnected-(U3-P7.6{slash}TB0.4-Pad59)") (class "Default")
      (node (ref "U3") (pin "59") (pinfunction "P7.6/TB0.4_59") (pintype "bidirectional+no_connect"))
    )
    (net (code "83") (name "unconnected-(U3-P7.7{slash}TB0CLK{slash}MCLK-Pad60)") (class "Default")
      (node (ref "U3") (pin "60") (pinfunction "P7.7/TB0CLK/MCLK_60") (pintype "bidirectional+no_connect"))
    )
    (net (code "84") (name "unconnected-(U3-P8.0-Pad15)") (class "Default")
      (node (ref "U3") (pin "15") (pinfunction "P8.0_15") (pintype "bidirectional+no_connect"))
    )
    (net (code "85") (name "unconnected-(U3-P8.1-Pad16)") (class "Default")
      (node (ref "U3") (pin "16") (pinfunction "P8.1_16") (pintype "bidirectional+no_connect"))
    )
    (net (code "86") (name "unconnected-(U3-P8.2-Pad17)") (class "Default")
      (node (ref "U3") (pin "17") (pinfunction "P8.2_17") (pintype "bidirectional+no_connect"))
    )
    (net (code "87") (name "unconnected-(U3-PJ.0{slash}TDO-Pad72)") (class "Default")
      (node (ref "U3") (pin "72") (pinfunction "PJ.0/TDO_72") (pintype "bidirectional+no_connect"))
    )
    (net (code "88") (name "unconnected-(U3-PJ.1{slash}TDI{slash}TCLK-Pad73)") (class "Default")
      (node (ref "U3") (pin "73") (pinfunction "PJ.1/TDI/TCLK_73") (pintype "bidirectional+no_connect"))
    )
    (net (code "89") (name "unconnected-(U3-PJ.2{slash}TMS-Pad74)") (class "Default")
      (node (ref "U3") (pin "74") (pinfunction "PJ.2/TMS_74") (pintype "bidirectional+no_connect"))
    )
    (net (code "90") (name "unconnected-(U3-PJ.3{slash}TCK-Pad75)") (class "Default")
      (node (ref "U3") (pin "75") (pinfunction "PJ.3/TCK_75") (pintype "bidirectional+no_connect"))
    )
  )
)
